# Schematic.net
KiCad netlist of a schematic drawn in EAGLE
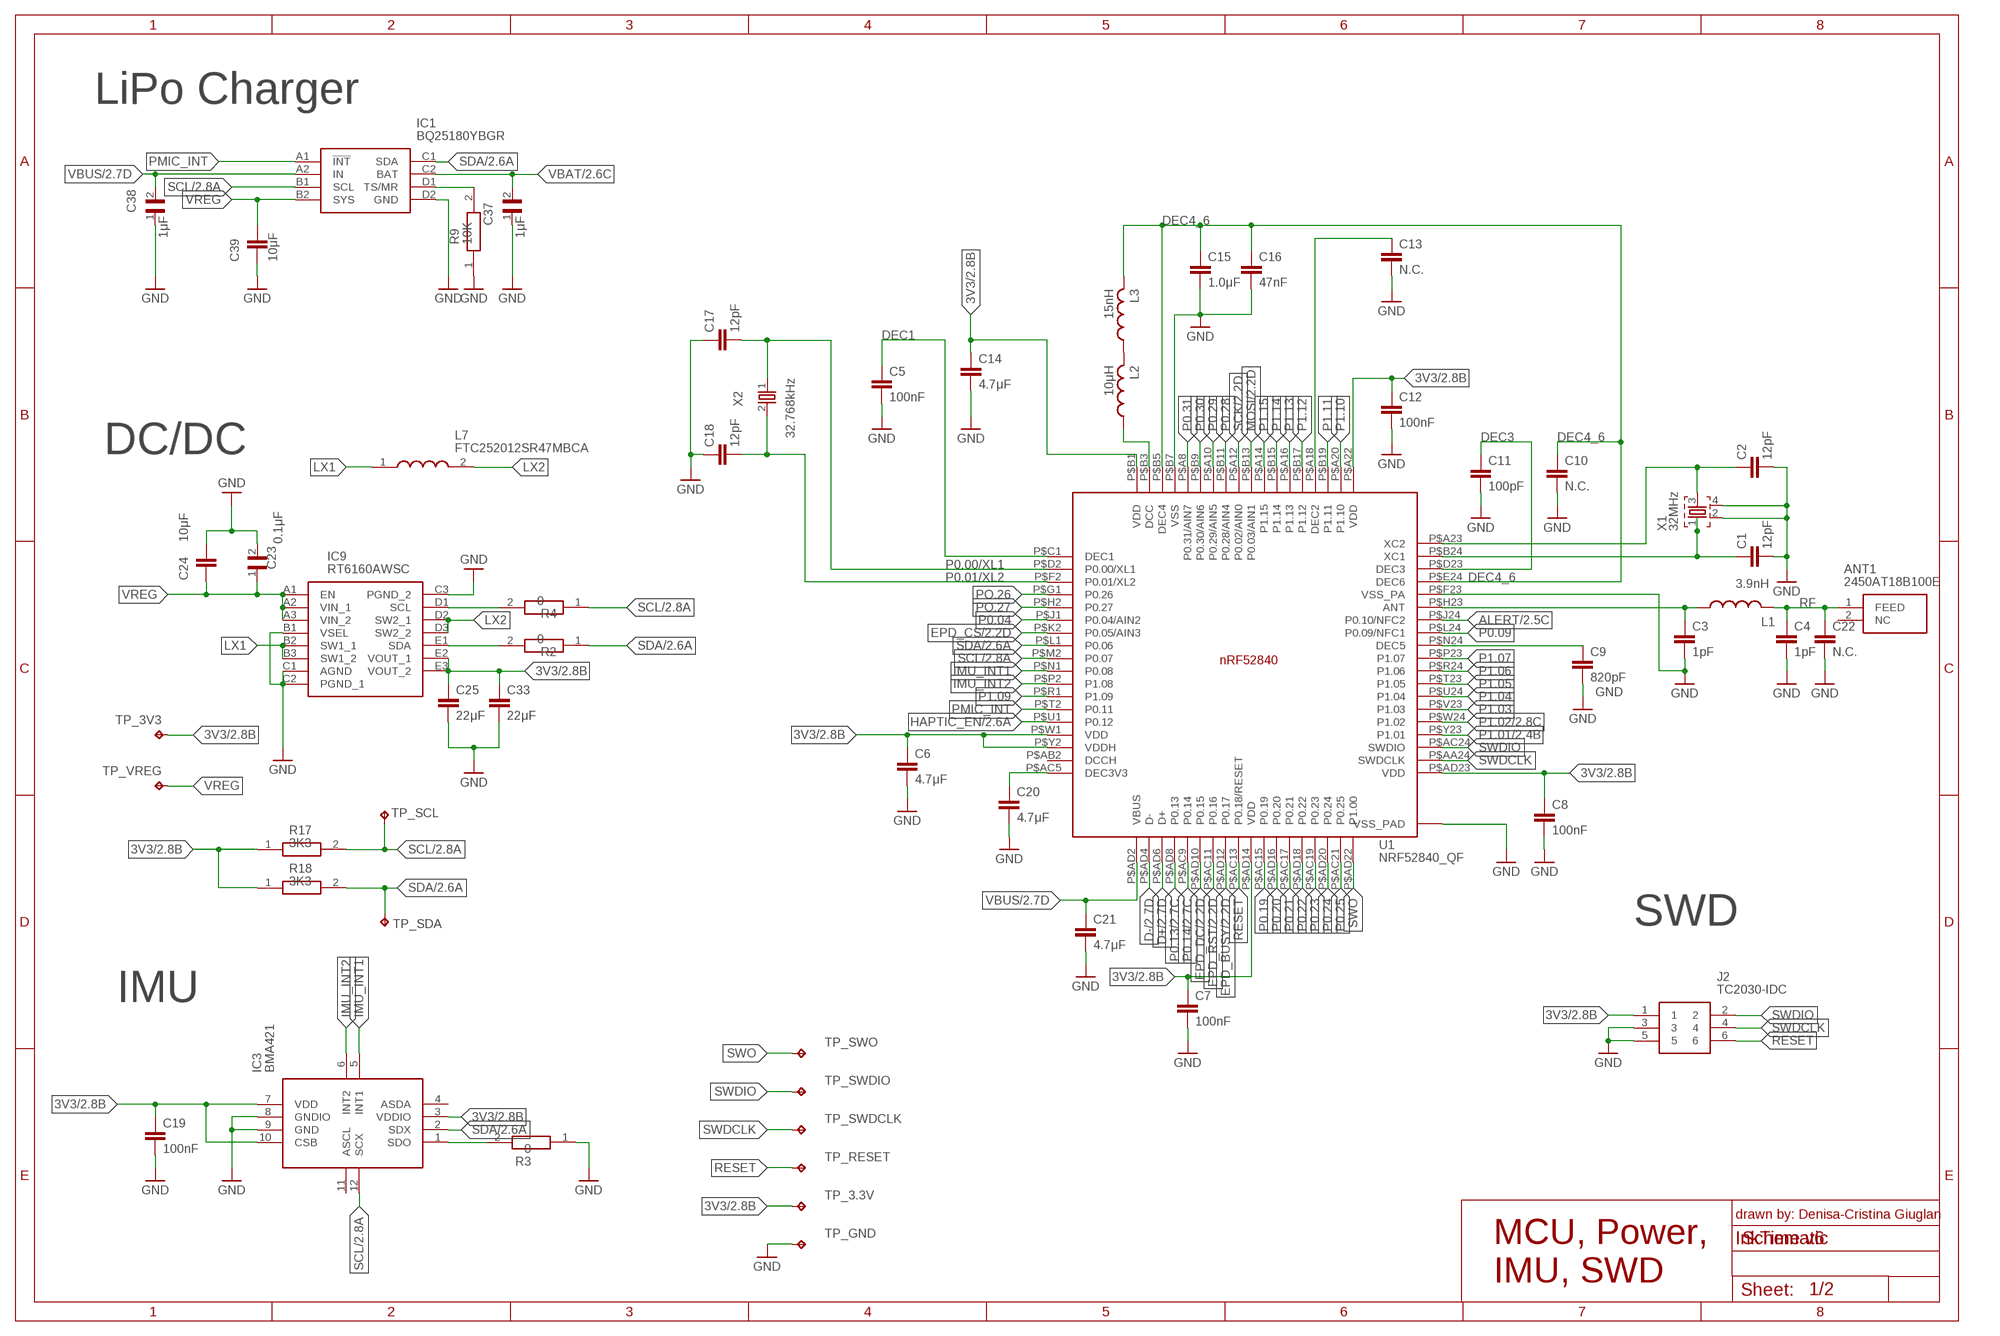
[diagram p0: schematic, sheet 1]
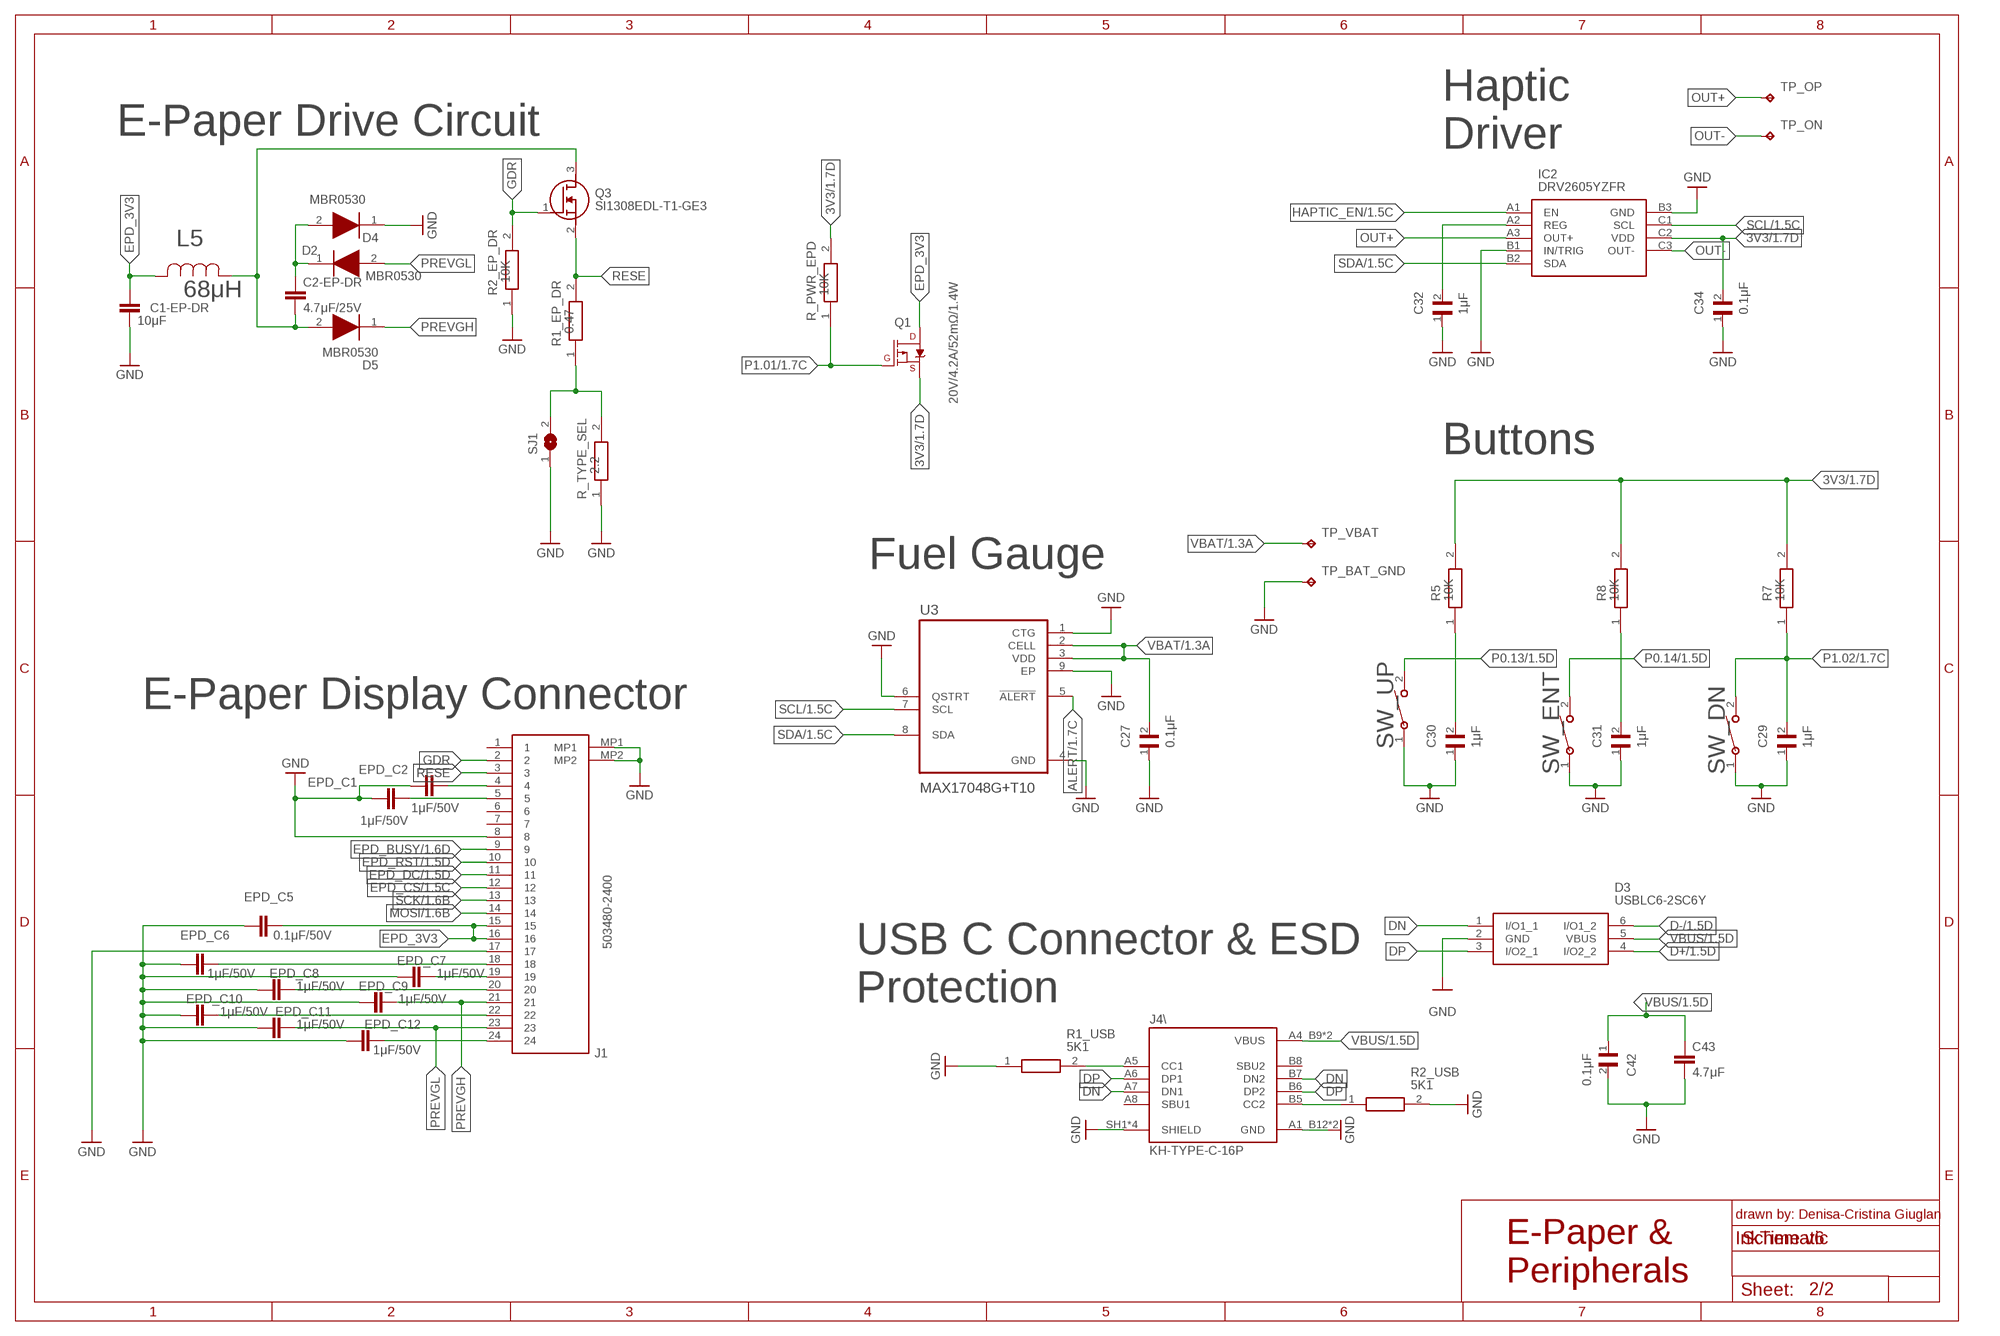
[diagram p1: schematic, sheet 2]

(export (version "E")
  (design (tool "Eeschema 10.0.6"))
  (components
    (comp (ref "ANT1")
      (value "2450AT18B100E")
      (footprint "eagle-import:2450AT18B100E_ANTC3216X140N")
      (fields (field (name "MOUSER_PART_NUMBER") "609-2450AT18B100E"))
      (libsource (lib "eagle-import") (part "2450AT18B100E_2450AT18B100E"))
    )
    (comp (ref "C1")
      (value "12pF")
      (footprint "eagle-import:NORDIC_NRF_3_RESC0201_L")
      (libsource (lib "eagle-import") (part "NORDIC_NRF_3_CAPACITOR_0201_L"))
    )
    (comp (ref "C2")
      (value "12pF")
      (footprint "eagle-import:NORDIC_NRF_3_RESC0201_L")
      (libsource (lib "eagle-import") (part "NORDIC_NRF_3_CAPACITOR_0201_L"))
    )
    (comp (ref "C3")
      (value "1pF")
      (footprint "eagle-import:NORDIC_NRF_3_RESC0402_N")
      (libsource (lib "eagle-import") (part "NORDIC_NRF_3_CAPACITOR_0402_N"))
    )
    (comp (ref "C4")
      (value "1pF")
      (footprint "eagle-import:NORDIC_NRF_3_RESC0201_L")
      (libsource (lib "eagle-import") (part "NORDIC_NRF_3_CAPACITOR_0201_L"))
    )
    (comp (ref "C5")
      (value "100nF")
      (footprint "eagle-import:NORDIC_NRF_3_RESC0201_L")
      (libsource (lib "eagle-import") (part "NORDIC_NRF_3_CAPACITOR_0201_L"))
    )
    (comp (ref "C6")
      (value "4.7μF")
      (footprint "eagle-import:NORDIC_NRF_3_RESC0402_N")
      (libsource (lib "eagle-import") (part "NORDIC_NRF_3_CAPACITOR_0402_N"))
    )
    (comp (ref "C7")
      (value "100nF")
      (footprint "eagle-import:NORDIC_NRF_3_RESC0201_L")
      (libsource (lib "eagle-import") (part "NORDIC_NRF_3_CAPACITOR_0201_L"))
    )
    (comp (ref "C8")
      (value "100nF")
      (footprint "eagle-import:NORDIC_NRF_3_RESC0201_L")
      (libsource (lib "eagle-import") (part "NORDIC_NRF_3_CAPACITOR_0201_L"))
    )
    (comp (ref "C9")
      (value "820pF")
      (footprint "eagle-import:NORDIC_NRF_3_RESC0201_L")
      (libsource (lib "eagle-import") (part "NORDIC_NRF_3_CAPACITOR_0201_L"))
    )
    (comp (ref "C10")
      (value "N.C.")
      (footprint "eagle-import:NORDIC_NRF_3_RESC0402_N")
      (libsource (lib "eagle-import") (part "NORDIC_NRF_3_CAPACITOR_0402_N"))
    )
    (comp (ref "C11")
      (value "100pF")
      (footprint "eagle-import:NORDIC_NRF_3_RESC0402_N")
      (libsource (lib "eagle-import") (part "NORDIC_NRF_3_CAPACITOR_0402_N"))
    )
    (comp (ref "C12")
      (value "100nF")
      (footprint "eagle-import:NORDIC_NRF_3_RESC0201_L")
      (libsource (lib "eagle-import") (part "NORDIC_NRF_3_CAPACITOR_0201_L"))
    )
    (comp (ref "C13")
      (value "N.C.")
      (footprint "eagle-import:NORDIC_NRF_3_RESC0402_N")
      (libsource (lib "eagle-import") (part "NORDIC_NRF_3_CAPACITOR_0402_N"))
    )
    (comp (ref "C14")
      (value "4.7μF")
      (footprint "eagle-import:NORDIC_NRF_3_RESC0402_N")
      (libsource (lib "eagle-import") (part "NORDIC_NRF_3_CAPACITOR_0402_N"))
    )
    (comp (ref "C15")
      (value "1.0μF")
      (footprint "eagle-import:NORDIC_NRF_3_RESC0402_N")
      (libsource (lib "eagle-import") (part "NORDIC_NRF_3_CAPACITOR_0402_N"))
    )
    (comp (ref "C16")
      (value "47nF")
      (footprint "eagle-import:NORDIC_NRF_3_RESC0201_L")
      (libsource (lib "eagle-import") (part "NORDIC_NRF_3_CAPACITOR_0201_L"))
    )
    (comp (ref "C17")
      (value "12pF")
      (footprint "eagle-import:NORDIC_NRF_3_RESC0201_L")
      (libsource (lib "eagle-import") (part "NORDIC_NRF_3_CAPACITOR_0201_L"))
    )
    (comp (ref "C18")
      (value "12pF")
      (footprint "eagle-import:NORDIC_NRF_3_RESC0201_L")
      (libsource (lib "eagle-import") (part "NORDIC_NRF_3_CAPACITOR_0201_L"))
    )
    (comp (ref "C19")
      (value "100nF")
      (footprint "eagle-import:NORDIC_NRF_3_RESC0201_L")
      (libsource (lib "eagle-import") (part "NORDIC_NRF_3_CAPACITOR_0201_L"))
    )
    (comp (ref "C20")
      (value "4.7μF")
      (footprint "eagle-import:NORDIC_NRF_3_RESC0402_N")
      (libsource (lib "eagle-import") (part "NORDIC_NRF_3_CAPACITOR_0402_N"))
    )
    (comp (ref "C21")
      (value "4.7μF")
      (footprint "eagle-import:NORDIC_NRF_3_RESC0402_N")
      (libsource (lib "eagle-import") (part "NORDIC_NRF_3_CAPACITOR_0402_N"))
    )
    (comp (ref "C22")
      (value "N.C.")
      (footprint "eagle-import:NORDIC_NRF_3_RESC0402_N")
      (libsource (lib "eagle-import") (part "NORDIC_NRF_3_CAPACITOR_0402_N"))
    )
    (comp (ref "C23")
      (value "0.1μF")
      (footprint "eagle-import:GRM011R60J152KE01L_2_CAPC0201X13N")
      (fields (field (name "MF") "Murata") (field (name "MP") "GRM011R60J152KE01L"))
      (libsource (lib "eagle-import") (part "GRM011R60J152KE01L_2_GRM011R60J152KE01L"))
    )
    (comp (ref "C24")
      (value "10μF")
      (footprint "eagle-import:NORDIC_NRF_3_RESC0402_N")
      (libsource (lib "eagle-import") (part "NORDIC_NRF_3_CAPACITOR_0402_N"))
    )
    (comp (ref "C25")
      (value "22μF")
      (footprint "eagle-import:NORDIC_NRF_3_RESC0402_N")
      (libsource (lib "eagle-import") (part "NORDIC_NRF_3_CAPACITOR_0402_N"))
    )
    (comp (ref "C33")
      (value "22μF")
      (footprint "eagle-import:NORDIC_NRF_3_RESC0402_N")
      (libsource (lib "eagle-import") (part "NORDIC_NRF_3_CAPACITOR_0402_N"))
    )
    (comp (ref "C37")
      (value "1μF")
      (footprint "eagle-import:GRM011R60J152KE01L_2_CAPC0201X13N")
      (fields (field (name "MF") "Murata") (field (name "MP") "GRM011R60J152KE01L"))
      (libsource (lib "eagle-import") (part "GRM011R60J152KE01L_2_GRM011R60J152KE01L"))
    )
    (comp (ref "C38")
      (value "1μF")
      (footprint "eagle-import:GRM011R60J152KE01L_2_CAPC0201X13N")
      (fields (field (name "MF") "Murata") (field (name "MP") "GRM011R60J152KE01L"))
      (libsource (lib "eagle-import") (part "GRM011R60J152KE01L_2_GRM011R60J152KE01L"))
    )
    (comp (ref "C39")
      (value "10μF")
      (footprint "eagle-import:NORDIC_NRF_3_RESC0402_N")
      (libsource (lib "eagle-import") (part "NORDIC_NRF_3_CAPACITOR_0402_N"))
    )
    (comp (ref "IC1")
      (value "BQ25180YBGR")
      (footprint "eagle-import:BQ25180YBGR_BGA8C40P2X4_100X155X50")
      (fields (field (name "MOUSER_PART_NUMBER") "595-BQ25180YBGR"))
      (libsource (lib "eagle-import") (part "BQ25180YBGR_BQ25180YBGR"))
    )
    (comp (ref "IC3")
      (value "BMA421")
      (footprint "eagle-import:BMA423_BMA423")
      (fields (field (name "ARROW_PART_NUMBER") "BMA423") (field (name "MOUSER_PART_NUMBER") "262-BMA423"))
      (libsource (lib "eagle-import") (part "BMA423_BMA423"))
    )
    (comp (ref "IC9")
      (value "RT6160AWSC")
      (footprint "eagle-import:RT6160AWSC_BGA15C40P3X5_140X230X60")
      (fields (field (name "MOUSER_PART_NUMBER") "835-RT6160AWSC"))
      (libsource (lib "eagle-import") (part "RT6160AWSC_RT6160AWSC"))
    )
    (comp (ref "J2")
      (value "TC2030-IDC")
      (footprint "eagle-import:TC2030-IDC_TC2030IDC")
      (libsource (lib "eagle-import") (part "TC2030-IDC_TC2030-IDC"))
    )
    (comp (ref "L1")
      (value "3.9nH")
      (footprint "eagle-import:NORDIC_NRF_2_RESC0402_L")
      (libsource (lib "eagle-import") (part "NORDIC_NRF_2_INDUCTOR_0402_L"))
    )
    (comp (ref "L2")
      (value "10μH")
      (footprint "eagle-import:NORDIC_NRF_2_RESC0402_L")
      (libsource (lib "eagle-import") (part "NORDIC_NRF_2_INDUCTOR_0402_L"))
    )
    (comp (ref "L3")
      (value "15nH")
      (footprint "eagle-import:NORDIC_NRF_2_RESC0402_L")
      (libsource (lib "eagle-import") (part "NORDIC_NRF_2_INDUCTOR_0402_L"))
    )
    (comp (ref "L7")
      (value "FTC252012SR47MBCA")
      (footprint "eagle-import:MLP2016SR47MT0S1_INDC2016X100N")
      (libsource (lib "eagle-import") (part "MLP2016SR47MT0S1_FTC252012SR47MBCA"))
    )
    (comp (ref "R2")
      (value "0")
      (footprint "eagle-import:CPF0201D7K68C1_0201")
      (libsource (lib "eagle-import") (part "CPF0201D7K68C1_CPF0201D7K68C1"))
    )
    (comp (ref "R3")
      (value "0")
      (footprint "eagle-import:CPF0201D7K68C1_0201")
      (libsource (lib "eagle-import") (part "CPF0201D7K68C1_CPF0201D7K68C1"))
    )
    (comp (ref "R4")
      (value "0")
      (footprint "eagle-import:CPF0201D7K68C1_0201")
      (libsource (lib "eagle-import") (part "CPF0201D7K68C1_CPF0201D7K68C1"))
    )
    (comp (ref "R9")
      (value "10K")
      (footprint "eagle-import:CPF0201D7K68C1_0201")
      (libsource (lib "eagle-import") (part "CPF0201D7K68C1_CPF0201D7K68C1"))
    )
    (comp (ref "R17")
      (value "3K3")
      (footprint "eagle-import:CPF0201D7K68C1_0201")
      (libsource (lib "eagle-import") (part "CPF0201D7K68C1_CPF0201D7K68C1"))
    )
    (comp (ref "R18")
      (value "3K3")
      (footprint "eagle-import:CPF0201D7K68C1_0201")
      (libsource (lib "eagle-import") (part "CPF0201D7K68C1_CPF0201D7K68C1"))
    )
    (comp (ref "TP_3.3V")
      (value "HECTOR_WATCH_1_TPTP20R")
      (footprint "eagle-import:HECTOR_WATCH_1_TP20R")
      (libsource (lib "eagle-import") (part "HECTOR_WATCH_1_TPTP20R"))
    )
    (comp (ref "TP_3V3")
      (value "HECTOR_WATCH_1_TPTP20R")
      (footprint "eagle-import:HECTOR_WATCH_1_TP20R")
      (libsource (lib "eagle-import") (part "HECTOR_WATCH_1_TPTP20R"))
    )
    (comp (ref "TP_GND")
      (value "HECTOR_WATCH_1_TPTP20R")
      (footprint "eagle-import:HECTOR_WATCH_1_TP20R")
      (libsource (lib "eagle-import") (part "HECTOR_WATCH_1_TPTP20R"))
    )
    (comp (ref "TP_RESET")
      (value "HECTOR_WATCH_1_TPTP20R")
      (footprint "eagle-import:HECTOR_WATCH_1_TP20R")
      (libsource (lib "eagle-import") (part "HECTOR_WATCH_1_TPTP20R"))
    )
    (comp (ref "TP_SCL")
      (value "HECTOR_WATCH_1_TPTP20R")
      (footprint "eagle-import:HECTOR_WATCH_1_TP20R")
      (libsource (lib "eagle-import") (part "HECTOR_WATCH_1_TPTP20R"))
    )
    (comp (ref "TP_SDA")
      (value "HECTOR_WATCH_1_TPTP20R")
      (footprint "eagle-import:HECTOR_WATCH_1_TP20R")
      (libsource (lib "eagle-import") (part "HECTOR_WATCH_1_TPTP20R"))
    )
    (comp (ref "TP_SWDCLK")
      (value "HECTOR_WATCH_1_TPTP20R")
      (footprint "eagle-import:HECTOR_WATCH_1_TP20R")
      (libsource (lib "eagle-import") (part "HECTOR_WATCH_1_TPTP20R"))
    )
    (comp (ref "TP_SWDIO")
      (value "HECTOR_WATCH_1_TPTP20R")
      (footprint "eagle-import:HECTOR_WATCH_1_TP20R")
      (libsource (lib "eagle-import") (part "HECTOR_WATCH_1_TPTP20R"))
    )
    (comp (ref "TP_SWO")
      (value "HECTOR_WATCH_1_TPTP20R")
      (footprint "eagle-import:HECTOR_WATCH_1_TP20R")
      (libsource (lib "eagle-import") (part "HECTOR_WATCH_1_TPTP20R"))
    )
    (comp (ref "TP_VREG")
      (value "HECTOR_WATCH_1_TPTP20R")
      (footprint "eagle-import:HECTOR_WATCH_1_TP20R")
      (libsource (lib "eagle-import") (part "HECTOR_WATCH_1_TPTP20R"))
    )
    (comp (ref "U1")
      (value "NRF52840_QF")
      (footprint "eagle-import:NORDIC_NRF_4_AQFN50P700X700X85_HS-74N")
      (libsource (lib "eagle-import") (part "NORDIC_NRF_4_NRF52840_QF"))
    )
    (comp (ref "X1")
      (value "32MHz")
      (footprint "eagle-import:NORDIC_NRF_BT-XTAL_2016_N")
      (libsource (lib "eagle-import") (part "NORDIC_NRF_XTAL_32MHZ"))
    )
    (comp (ref "X2")
      (value "32.768kHz")
      (footprint "eagle-import:NORDIC_NRF_1_XTAL_3215_N")
      (libsource (lib "eagle-import") (part "NORDIC_NRF_1_XTAL_32KHZ"))
    )
    (comp (ref "C1-EP-DR")
      (value "10μF")
      (footprint "eagle-import:NORDIC_NRF_3_RESC0402_N")
      (libsource (lib "eagle-import") (part "NORDIC_NRF_3_CAPACITOR_0402_N"))
    )
    (comp (ref "C2-EP-DR")
      (value "4.7μF/25V")
      (footprint "eagle-import:NORDIC_NRF_3_RESC0402_N")
      (libsource (lib "eagle-import") (part "NORDIC_NRF_3_CAPACITOR_0402_N"))
    )
    (comp (ref "C27")
      (value "0.1μF")
      (footprint "eagle-import:GRM011R60J152KE01L_2_CAPC0201X13N")
      (fields (field (name "MF") "Murata") (field (name "MP") "GRM011R60J152KE01L"))
      (libsource (lib "eagle-import") (part "GRM011R60J152KE01L_2_GRM011R60J152KE01L"))
    )
    (comp (ref "C29")
      (value "1μF")
      (footprint "eagle-import:GRM011R60J152KE01L_2_CAPC0201X13N")
      (fields (field (name "MF") "Murata") (field (name "MP") "GRM011R60J152KE01L"))
      (libsource (lib "eagle-import") (part "GRM011R60J152KE01L_2_GRM011R60J152KE01L"))
    )
    (comp (ref "C30")
      (value "1μF")
      (footprint "eagle-import:GRM011R60J152KE01L_2_CAPC0201X13N")
      (fields (field (name "MF") "Murata") (field (name "MP") "GRM011R60J152KE01L"))
      (libsource (lib "eagle-import") (part "GRM011R60J152KE01L_2_GRM011R60J152KE01L"))
    )
    (comp (ref "C31")
      (value "1μF")
      (footprint "eagle-import:GRM011R60J152KE01L_2_CAPC0201X13N")
      (fields (field (name "MF") "Murata") (field (name "MP") "GRM011R60J152KE01L"))
      (libsource (lib "eagle-import") (part "GRM011R60J152KE01L_2_GRM011R60J152KE01L"))
    )
    (comp (ref "C32")
      (value "1μF")
      (footprint "eagle-import:GRM011R60J152KE01L_2_CAPC0201X13N")
      (fields (field (name "MF") "Murata") (field (name "MP") "GRM011R60J152KE01L"))
      (libsource (lib "eagle-import") (part "GRM011R60J152KE01L_2_GRM011R60J152KE01L"))
    )
    (comp (ref "C34")
      (value "0.1μF")
      (footprint "eagle-import:GRM011R60J152KE01L_2_CAPC0201X13N")
      (fields (field (name "MF") "Murata") (field (name "MP") "GRM011R60J152KE01L"))
      (libsource (lib "eagle-import") (part "GRM011R60J152KE01L_2_GRM011R60J152KE01L"))
    )
    (comp (ref "C42")
      (value "0.1μF")
      (footprint "eagle-import:GRM011R60J152KE01L_2_CAPC0201X13N")
      (fields (field (name "MF") "Murata") (field (name "MP") "GRM011R60J152KE01L"))
      (libsource (lib "eagle-import") (part "GRM011R60J152KE01L_2_GRM011R60J152KE01L"))
    )
    (comp (ref "C43")
      (value "4.7μF")
      (footprint "eagle-import:NORDIC_NRF_3_RESC0402_N")
      (libsource (lib "eagle-import") (part "NORDIC_NRF_3_CAPACITOR_0402_N"))
    )
    (comp (ref "D2")
      (value "MBR0530")
      (footprint "eagle-import:ESP32_C6_LIBRARY_5_SOD3716X135N")
      (fields (field (name "MF") "ON Semiconductor"))
      (libsource (lib "eagle-import") (part "ESP32_C6_LIBRARY_5_MBR0530"))
    )
    (comp (ref "D3")
      (value "USBLC6-2SC6Y")
      (footprint "eagle-import:ESP32_C6_LIBRARY_3_SOT95P280X145-6N")
      (fields (field (name "MF") "STMicroelectronics"))
      (libsource (lib "eagle-import") (part "ESP32_C6_LIBRARY_3_USBLC6-2SC6Y"))
    )
    (comp (ref "D4")
      (value "MBR0530")
      (footprint "eagle-import:ESP32_C6_LIBRARY_5_SOD3716X135N")
      (fields (field (name "MF") "ON Semiconductor"))
      (libsource (lib "eagle-import") (part "ESP32_C6_LIBRARY_5_MBR0530"))
    )
    (comp (ref "D5")
      (value "MBR0530")
      (footprint "eagle-import:ESP32_C6_LIBRARY_5_SOD3716X135N")
      (fields (field (name "MF") "ON Semiconductor"))
      (libsource (lib "eagle-import") (part "ESP32_C6_LIBRARY_5_MBR0530"))
    )
    (comp (ref "EPD_C1")
      (value "1μF/50V")
      (footprint "eagle-import:NORDIC_NRF_3_RESC0402_N")
      (libsource (lib "eagle-import") (part "NORDIC_NRF_3_CAPACITOR_0402_N"))
    )
    (comp (ref "EPD_C2")
      (value "1μF/50V")
      (footprint "eagle-import:NORDIC_NRF_3_RESC0402_N")
      (libsource (lib "eagle-import") (part "NORDIC_NRF_3_CAPACITOR_0402_N"))
    )
    (comp (ref "EPD_C5")
      (value "0.1μF/50V")
      (footprint "eagle-import:NORDIC_NRF_3_RESC0402_N")
      (libsource (lib "eagle-import") (part "NORDIC_NRF_3_CAPACITOR_0402_N"))
    )
    (comp (ref "EPD_C6")
      (value "1μF/50V")
      (footprint "eagle-import:NORDIC_NRF_3_RESC0402_N")
      (libsource (lib "eagle-import") (part "NORDIC_NRF_3_CAPACITOR_0402_N"))
    )
    (comp (ref "EPD_C7")
      (value "1μF/50V")
      (footprint "eagle-import:NORDIC_NRF_3_RESC0402_N")
      (libsource (lib "eagle-import") (part "NORDIC_NRF_3_CAPACITOR_0402_N"))
    )
    (comp (ref "EPD_C8")
      (value "1μF/50V")
      (footprint "eagle-import:NORDIC_NRF_3_RESC0402_N")
      (libsource (lib "eagle-import") (part "NORDIC_NRF_3_CAPACITOR_0402_N"))
    )
    (comp (ref "EPD_C9")
      (value "1μF/50V")
      (footprint "eagle-import:NORDIC_NRF_3_RESC0402_N")
      (libsource (lib "eagle-import") (part "NORDIC_NRF_3_CAPACITOR_0402_N"))
    )
    (comp (ref "EPD_C10")
      (value "1μF/50V")
      (footprint "eagle-import:NORDIC_NRF_3_RESC0402_N")
      (libsource (lib "eagle-import") (part "NORDIC_NRF_3_CAPACITOR_0402_N"))
    )
    (comp (ref "EPD_C11")
      (value "1μF/50V")
      (footprint "eagle-import:NORDIC_NRF_3_RESC0402_N")
      (libsource (lib "eagle-import") (part "NORDIC_NRF_3_CAPACITOR_0402_N"))
    )
    (comp (ref "EPD_C12")
      (value "1μF/50V")
      (footprint "eagle-import:NORDIC_NRF_3_RESC0402_N")
      (libsource (lib "eagle-import") (part "NORDIC_NRF_3_CAPACITOR_0402_N"))
    )
    (comp (ref "IC2")
      (value "DRV2605YZFR")
      (footprint "eagle-import:DRV2605YZFR_BGA9C50P3X3_144X144X62")
      (libsource (lib "eagle-import") (part "DRV2605YZFR_DRV2605YZFR"))
    )
    (comp (ref "J1")
      (value "503480-2400")
      (footprint "eagle-import:503480-2400_5034802400")
      (fields (field (name "MOUSER_PART_NUMBER") "538-503480-2400"))
      (libsource (lib "eagle-import") (part "503480-2400_503480-2400"))
    )
    (comp (ref "J4\\")
      (value "KH-TYPE-C-16P")
      (footprint "eagle-import:KH-TYPE-C-16P_KINGHELM_KH-TYPE-C-16P")
      (fields (field (name "MF") "kinghelm"))
      (libsource (lib "eagle-import") (part "KH-TYPE-C-16P_KH-TYPE-C-16P"))
    )
    (comp (ref "L5")
      (value "68μH")
      (footprint "eagle-import:ESP32_C6_LIBRARY_2_IND_4828-WE-TPC_WRE")
      (fields
        (field (name "MANUFACTURER_PART_NUMBER") "744043680")
        (field (name "COPYRIGHT") "Copyright (C) 2024 Ultra Librarian. All rights reserved.")
      )
      (libsource (lib "eagle-import") (part "ESP32_C6_LIBRARY_2_744043680IND_4828-WE-TPC_WRE"))
    )
    (comp (ref "Q1")
      (value "20V/4.2A/52mΩ/1.4W")
      (footprint "eagle-import:ESP32_C6_LIBRARY_4_ESP32_C6_LIBRARY_4_ESP32_C6_LIBRARY_4_ESP32_C6_LIBRARY_4_ESP32_WROVER_SPARKFUN-DISCRETESEMI_SOT23-3")
      (libsource (lib "eagle-import") (part "ESP32_C6_LIBRARY_4_ESP32_WROVER_SPARKFUN-DISCRETESEMI_MOSFET_PCH-DMG2305UX-7"))
    )
    (comp (ref "Q3")
      (value "SI1308EDL-T1-GE3")
      (footprint "eagle-import:ESP32_C6_LIBRARY_6_SOT65P210X110-3N")
      (fields (field (name "MF") "Vishay Siliconix"))
      (libsource (lib "eagle-import") (part "ESP32_C6_LIBRARY_6_SI1308EDL-T1-GE3"))
    )
    (comp (ref "R1_EP_DR")
      (value "0.47")
      (footprint "eagle-import:CPF0201D7K68C1_0201")
      (libsource (lib "eagle-import") (part "CPF0201D7K68C1_CPF0201D7K68C1"))
    )
    (comp (ref "R1_USB")
      (value "5K1")
      (footprint "eagle-import:CPF0201D7K68C1_0201")
      (libsource (lib "eagle-import") (part "CPF0201D7K68C1_CPF0201D7K68C1"))
    )
    (comp (ref "R2_EP_DR")
      (value "10K")
      (footprint "eagle-import:CPF0201D7K68C1_0201")
      (libsource (lib "eagle-import") (part "CPF0201D7K68C1_CPF0201D7K68C1"))
    )
    (comp (ref "R2_USB")
      (value "5K1")
      (footprint "eagle-import:CPF0201D7K68C1_0201")
      (libsource (lib "eagle-import") (part "CPF0201D7K68C1_CPF0201D7K68C1"))
    )
    (comp (ref "R5")
      (value "10K")
      (footprint "eagle-import:CPF0201D7K68C1_0201")
      (libsource (lib "eagle-import") (part "CPF0201D7K68C1_CPF0201D7K68C1"))
    )
    (comp (ref "R7")
      (value "10K")
      (footprint "eagle-import:CPF0201D7K68C1_0201")
      (libsource (lib "eagle-import") (part "CPF0201D7K68C1_CPF0201D7K68C1"))
    )
    (comp (ref "R8")
      (value "10K")
      (footprint "eagle-import:CPF0201D7K68C1_0201")
      (libsource (lib "eagle-import") (part "CPF0201D7K68C1_CPF0201D7K68C1"))
    )
    (comp (ref "R_PWR_EPD")
      (value "10K")
      (footprint "eagle-import:CPF0201D7K68C1_0201")
      (libsource (lib "eagle-import") (part "CPF0201D7K68C1_CPF0201D7K68C1"))
    )
    (comp (ref "R_TYPE_SEL")
      (value "2.2")
      (footprint "eagle-import:CPF0201D7K68C1_0201")
      (libsource (lib "eagle-import") (part "CPF0201D7K68C1_CPF0201D7K68C1"))
    )
    (comp (ref "SJ1")
      (value "ESP32_C6_LIBRARY_7_JUMPER_SJ")
      (footprint "eagle-import:ESP32_C6_LIBRARY_7_JUMPER_SJ")
      (libsource (lib "eagle-import") (part "ESP32_C6_LIBRARY_7_JUMPER_SJ"))
    )
    (comp (ref "SW_DN")
      (value "2025-10-22_07-23-44_LIBRARY_EVP-AKE31ASW_EVP-AKE31A_PAN")
      (footprint "eagle-import:2025-10-22_07-23-44_LIBRARY_SW_EVP-AKE31A_PAN")
      (fields
        (field (name "MANUFACTURER_PART_NUMBER") "EVP-AKE31A")
        (field (name "COPYRIGHT") "Copyright (C) 2025 Ultra Librarian. All rights reserved.")
      )
      (libsource (lib "eagle-import") (part "2025-10-22_07-23-44_LIBRARY_EVP-AKE31ASW_EVP-AKE31A_PAN"))
    )
    (comp (ref "SW_ENT")
      (value "2025-10-22_07-23-44_LIBRARY_EVP-AKE31ASW_EVP-AKE31A_PAN")
      (footprint "eagle-import:2025-10-22_07-23-44_LIBRARY_SW_EVP-AKE31A_PAN")
      (fields
        (field (name "MANUFACTURER_PART_NUMBER") "EVP-AKE31A")
        (field (name "COPYRIGHT") "Copyright (C) 2025 Ultra Librarian. All rights reserved.")
      )
      (libsource (lib "eagle-import") (part "2025-10-22_07-23-44_LIBRARY_EVP-AKE31ASW_EVP-AKE31A_PAN"))
    )
    (comp (ref "SW_UP")
      (value "2025-10-22_07-23-44_LIBRARY_EVP-AKE31ASW_EVP-AKE31A_PAN")
      (footprint "eagle-import:2025-10-22_07-23-44_LIBRARY_SW_EVP-AKE31A_PAN")
      (fields
        (field (name "MANUFACTURER_PART_NUMBER") "EVP-AKE31A")
        (field (name "COPYRIGHT") "Copyright (C) 2025 Ultra Librarian. All rights reserved.")
      )
      (libsource (lib "eagle-import") (part "2025-10-22_07-23-44_LIBRARY_EVP-AKE31ASW_EVP-AKE31A_PAN"))
    )
    (comp (ref "TP_BAT_GND")
      (value "HECTOR_WATCH_1_TPTP20R")
      (footprint "eagle-import:HECTOR_WATCH_1_TP20R")
      (libsource (lib "eagle-import") (part "HECTOR_WATCH_1_TPTP20R"))
    )
    (comp (ref "TP_ON")
      (value "HECTOR_WATCH_1_TPTP20R")
      (footprint "eagle-import:HECTOR_WATCH_1_TP20R")
      (libsource (lib "eagle-import") (part "HECTOR_WATCH_1_TPTP20R"))
    )
    (comp (ref "TP_OP")
      (value "HECTOR_WATCH_1_TPTP20R")
      (footprint "eagle-import:HECTOR_WATCH_1_TP20R")
      (libsource (lib "eagle-import") (part "HECTOR_WATCH_1_TPTP20R"))
    )
    (comp (ref "TP_VBAT")
      (value "HECTOR_WATCH_1_TPTP20R")
      (footprint "eagle-import:HECTOR_WATCH_1_TP20R")
      (libsource (lib "eagle-import") (part "HECTOR_WATCH_1_TPTP20R"))
    )
    (comp (ref "U3")
      (value "MAX17048G+T10")
      (footprint "eagle-import:ESP32_C6_LIBRARY_SON50P200X200X80-9N")
      (fields (field (name "MF") "Analog Devices"))
      (libsource (lib "eagle-import") (part "ESP32_C6_LIBRARY_MAX17048G+T10"))
    )
  )
  (nets
    (net (code "1") (name "3V3") (class "Default")
      (node (ref "C12") (pin "1") (pinfunction "1_1") (pintype "passive"))
      (node (ref "C14") (pin "1") (pinfunction "1_1") (pintype "passive"))
      (node (ref "C19") (pin "1") (pinfunction "1_1") (pintype "passive"))
      (node (ref "C25") (pin "1") (pinfunction "1_1") (pintype "passive"))
      (node (ref "C33") (pin "1") (pinfunction "1_1") (pintype "passive"))
      (node (ref "C34") (pin "2") (pinfunction "2_2") (pintype "passive"))
      (node (ref "C6") (pin "1") (pinfunction "1_1") (pintype "passive"))
      (node (ref "C7") (pin "1") (pinfunction "1_1") (pintype "passive"))
      (node (ref "C8") (pin "1") (pinfunction "1_1") (pintype "passive"))
      (node (ref "IC2") (pin "C2") (pinfunction "VDD_C2") (pintype "bidirectional"))
      (node (ref "IC3") (pin "10") (pinfunction "CSB_10") (pintype "bidirectional"))
      (node (ref "IC3") (pin "3") (pinfunction "VDDIO_3") (pintype "bidirectional"))
      (node (ref "IC3") (pin "7") (pinfunction "VDD_7") (pintype "bidirectional"))
      (node (ref "IC9") (pin "E2") (pinfunction "VOUT_1_E2") (pintype "bidirectional"))
      (node (ref "IC9") (pin "E3") (pinfunction "VOUT_2_E3") (pintype "bidirectional"))
      (node (ref "J2") (pin "1") (pinfunction "1_1") (pintype "bidirectional"))
      (node (ref "Q1") (pin "2") (pinfunction "S_2") (pintype "bidirectional"))
      (node (ref "R17") (pin "1") (pinfunction "1_1") (pintype "bidirectional"))
      (node (ref "R18") (pin "1") (pinfunction "1_1") (pintype "bidirectional"))
      (node (ref "R5") (pin "2") (pinfunction "2_2") (pintype "bidirectional"))
      (node (ref "R7") (pin "2") (pinfunction "2_2") (pintype "bidirectional"))
      (node (ref "R8") (pin "2") (pinfunction "2_2") (pintype "bidirectional"))
      (node (ref "R_PWR_EPD") (pin "2") (pinfunction "2_2") (pintype "bidirectional"))
      (node (ref "TP_3.3V") (pin "TP") (pinfunction "TP_TP") (pintype "input"))
      (node (ref "TP_3V3") (pin "TP") (pinfunction "TP_TP") (pintype "input"))
      (node (ref "U1") (pin "P$A22") (pinfunction "VDD_P$A22") (pintype "power_in"))
      (node (ref "U1") (pin "P$AD14") (pinfunction "VDD_P$AD14") (pintype "power_in"))
      (node (ref "U1") (pin "P$AD23") (pinfunction "VDD_P$AD23") (pintype "power_in"))
      (node (ref "U1") (pin "P$B1") (pinfunction "VDD_P$B1") (pintype "power_in"))
      (node (ref "U1") (pin "P$W1") (pinfunction "VDD_P$W1") (pintype "power_in"))
      (node (ref "U1") (pin "P$Y2") (pinfunction "VDDH_P$Y2") (pintype "power_in"))
    )
    (net (code "2") (name "ALERT") (class "Default")
      (node (ref "U1") (pin "P$J24") (pinfunction "P0.10/NFC2_P$J24") (pintype "bidirectional"))
      (node (ref "U3") (pin "5") (pinfunction "~{ALERT}_5") (pintype "output"))
    )
    (net (code "3") (name "D+") (class "Default")
      (node (ref "D3") (pin "4") (pinfunction "I/O2_2_4") (pintype "bidirectional"))
      (node (ref "U1") (pin "P$AD6") (pinfunction "D+_P$AD6") (pintype "bidirectional"))
    )
    (net (code "4") (name "D-") (class "Default")
      (node (ref "D3") (pin "6") (pinfunction "I/O1_2_6") (pintype "bidirectional"))
      (node (ref "U1") (pin "P$AD4") (pinfunction "D-_P$AD4") (pintype "bidirectional"))
    )
    (net (code "5") (name "DEC1") (class "Default")
      (node (ref "C5") (pin "1") (pinfunction "1_1") (pintype "passive"))
      (node (ref "U1") (pin "P$C1") (pinfunction "DEC1_P$C1") (pintype "power_in"))
    )
    (net (code "6") (name "DEC3") (class "Default")
      (node (ref "C11") (pin "1") (pinfunction "1_1") (pintype "passive"))
      (node (ref "U1") (pin "P$D23") (pinfunction "DEC3_P$D23") (pintype "bidirectional"))
    )
    (net (code "7") (name "DEC4_6") (class "Default")
      (node (ref "C10") (pin "1") (pinfunction "1_1") (pintype "passive"))
      (node (ref "C15") (pin "1") (pinfunction "1_1") (pintype "passive"))
      (node (ref "C16") (pin "1") (pinfunction "1_1") (pintype "passive"))
      (node (ref "L3") (pin "2") (pinfunction "2_2") (pintype "passive"))
      (node (ref "U1") (pin "P$B5") (pinfunction "DEC4_P$B5") (pintype "power_in"))
      (node (ref "U1") (pin "P$E24") (pinfunction "DEC6_P$E24") (pintype "bidirectional"))
    )
    (net (code "8") (name "DN") (class "Default")
      (node (ref "D3") (pin "1") (pinfunction "I/O1_1_1") (pintype "bidirectional"))
      (node (ref "J4\\") (pin "A7") (pinfunction "DN1_A7") (pintype "bidirectional"))
      (node (ref "J4\\") (pin "B7") (pinfunction "DN2_B7") (pintype "bidirectional"))
    )
    (net (code "9") (name "DP") (class "Default")
      (node (ref "D3") (pin "3") (pinfunction "I/O2_1_3") (pintype "bidirectional"))
      (node (ref "J4\\") (pin "A6") (pinfunction "DP1_A6") (pintype "bidirectional"))
      (node (ref "J4\\") (pin "B6") (pinfunction "DP2_B6") (pintype "bidirectional"))
    )
    (net (code "10") (name "EPD_3V3") (class "Default")
      (node (ref "C1-EP-DR") (pin "1") (pinfunction "1_1") (pintype "passive"))
      (node (ref "EPD_C5") (pin "2") (pinfunction "2_2") (pintype "passive"))
      (node (ref "J1") (pin "15") (pinfunction "15_15") (pintype "bidirectional"))
      (node (ref "J1") (pin "16") (pinfunction "16_16") (pintype "bidirectional"))
      (node (ref "L5") (pin "2") (pinfunction "2_2") (pintype "passive"))
      (node (ref "Q1") (pin "3") (pinfunction "D_3") (pintype "bidirectional"))
    )
    (net (code "11") (name "EPD_BUSY") (class "Default")
      (node (ref "J1") (pin "9") (pinfunction "9_9") (pintype "bidirectional"))
      (node (ref "U1") (pin "P$AD12") (pinfunction "P0.17_P$AD12") (pintype "bidirectional"))
    )
    (net (code "12") (name "EPD_CS") (class "Default")
      (node (ref "J1") (pin "12") (pinfunction "12_12") (pintype "bidirectional"))
      (node (ref "U1") (pin "P$K2") (pinfunction "P0.05/AIN3_P$K2") (pintype "bidirectional"))
    )
    (net (code "13") (name "EPD_DC") (class "Default")
      (node (ref "J1") (pin "11") (pinfunction "11_11") (pintype "bidirectional"))
      (node (ref "U1") (pin "P$AD10") (pinfunction "P0.15_P$AD10") (pintype "bidirectional"))
    )
    (net (code "14") (name "EPD_RST") (class "Default")
      (node (ref "J1") (pin "10") (pinfunction "10_10") (pintype "bidirectional"))
      (node (ref "U1") (pin "P$AC11") (pinfunction "P0.16_P$AC11") (pintype "bidirectional"))
    )
    (net (code "15") (name "GDR") (class "Default")
      (node (ref "J1") (pin "2") (pinfunction "2_2") (pintype "bidirectional"))
      (node (ref "Q3") (pin "1") (pinfunction "G_1") (pintype "bidirectional"))
      (node (ref "R2_EP_DR") (pin "2") (pinfunction "2_2") (pintype "bidirectional"))
    )
    (net (code "16") (name "GND") (class "Default")
      (node (ref "C1") (pin "2") (pinfunction "2_2") (pintype "passive"))
      (node (ref "C1-EP-DR") (pin "2") (pinfunction "2_2") (pintype "passive"))
      (node (ref "C10") (pin "2") (pinfunction "2_2") (pintype "passive"))
      (node (ref "C11") (pin "2") (pinfunction "2_2") (pintype "passive"))
      (node (ref "C12") (pin "2") (pinfunction "2_2") (pintype "passive"))
      (node (ref "C13") (pin "2") (pinfunction "2_2") (pintype "passive"))
      (node (ref "C14") (pin "2") (pinfunction "2_2") (pintype "passive"))
      (node (ref "C15") (pin "2") (pinfunction "2_2") (pintype "passive"))
      (node (ref "C16") (pin "2") (pinfunction "2_2") (pintype "passive"))
      (node (ref "C17") (pin "1") (pinfunction "1_1") (pintype "passive"))
      (node (ref "C18") (pin "1") (pinfunction "1_1") (pintype "passive"))
      (node (ref "C19") (pin "2") (pinfunction "2_2") (pintype "passive"))
      (node (ref "C2") (pin "2") (pinfunction "2_2") (pintype "passive"))
      (node (ref "C20") (pin "2") (pinfunction "2_2") (pintype "passive"))
      (node (ref "C21") (pin "2") (pinfunction "2_2") (pintype "passive"))
      (node (ref "C22") (pin "2") (pinfunction "2_2") (pintype "passive"))
      (node (ref "C23") (pin "2") (pinfunction "2_2") (pintype "passive"))
      (node (ref "C24") (pin "1") (pinfunction "1_1") (pintype "passive"))
      (node (ref "C25") (pin "2") (pinfunction "2_2") (pintype "passive"))
      (node (ref "C27") (pin "1") (pinfunction "1_1") (pintype "passive"))
      (node (ref "C29") (pin "1") (pinfunction "1_1") (pintype "passive"))
      (node (ref "C3") (pin "2") (pinfunction "2_2") (pintype "passive"))
      (node (ref "C30") (pin "1") (pinfunction "1_1") (pintype "passive"))
      (node (ref "C31") (pin "1") (pinfunction "1_1") (pintype "passive"))
      (node (ref "C32") (pin "1") (pinfunction "1_1") (pintype "passive"))
      (node (ref "C33") (pin "2") (pinfunction "2_2") (pintype "passive"))
      (node (ref "C34") (pin "1") (pinfunction "1_1") (pintype "passive"))
      (node (ref "C37") (pin "1") (pinfunction "1_1") (pintype "passive"))
      (node (ref "C38") (pin "1") (pinfunction "1_1") (pintype "passive"))
      (node (ref "C39") (pin "2") (pinfunction "2_2") (pintype "passive"))
      (node (ref "C4") (pin "2") (pinfunction "2_2") (pintype "passive"))
      (node (ref "C42") (pin "2") (pinfunction "2_2") (pintype "passive"))
      (node (ref "C43") (pin "2") (pinfunction "2_2") (pintype "passive"))
      (node (ref "C5") (pin "2") (pinfunction "2_2") (pintype "passive"))
      (node (ref "C6") (pin "2") (pinfunction "2_2") (pintype "passive"))
      (node (ref "C7") (pin "2") (pinfunction "2_2") (pintype "passive"))
      (node (ref "C8") (pin "2") (pinfunction "2_2") (pintype "passive"))
      (node (ref "C9") (pin "2") (pinfunction "2_2") (pintype "passive"))
      (node (ref "D3") (pin "2") (pinfunction "GND_2") (pintype "bidirectional"))
      (node (ref "D4") (pin "1") (pinfunction "K_1") (pintype "bidirectional"))
      (node (ref "EPD_C1") (pin "1") (pinfunction "1_1") (pintype "passive"))
      (node (ref "EPD_C10") (pin "1") (pinfunction "1_1") (pintype "passive"))
      (node (ref "EPD_C11") (pin "1") (pinfunction "1_1") (pintype "passive"))
      (node (ref "EPD_C12") (pin "1") (pinfunction "1_1") (pintype "passive"))
      (node (ref "EPD_C2") (pin "1") (pinfunction "1_1") (pintype "passive"))
      (node (ref "EPD_C5") (pin "1") (pinfunction "1_1") (pintype "passive"))
      (node (ref "EPD_C6") (pin "1") (pinfunction "1_1") (pintype "passive"))
      (node (ref "EPD_C7") (pin "1") (pinfunction "1_1") (pintype "passive"))
      (node (ref "EPD_C8") (pin "1") (pinfunction "1_1") (pintype "passive"))
      (node (ref "EPD_C9") (pin "1") (pinfunction "1_1") (pintype "passive"))
      (node (ref "IC1") (pin "D2") (pinfunction "GND_D2") (pintype "bidirectional"))
      (node (ref "IC2") (pin "B1") (pinfunction "IN/TRIG_B1") (pintype "bidirectional"))
      (node (ref "IC2") (pin "B3") (pinfunction "GND_B3") (pintype "bidirectional"))
      (node (ref "IC3") (pin "8") (pinfunction "GNDIO_8") (pintype "bidirectional"))
      (node (ref "IC3") (pin "9") (pinfunction "GND_9") (pintype "bidirectional"))
      (node (ref "IC9") (pin "B1") (pinfunction "VSEL_B1") (pintype "bidirectional"))
      (node (ref "IC9") (pin "C1") (pinfunction "AGND_C1") (pintype "bidirectional"))
      (node (ref "IC9") (pin "C2") (pinfunction "PGND_1_C2") (pintype "bidirectional"))
      (node (ref "IC9") (pin "C3") (pinfunction "PGND_2_C3") (pintype "bidirectional"))
      (node (ref "J1") (pin "17") (pinfunction "17_17") (pintype "bidirectional"))
      (node (ref "J1") (pin "8") (pinfunction "8_8") (pintype "bidirectional"))
      (node (ref "J1") (pin "MP1") (pinfunction "MP1_MP1") (pintype "bidirectional"))
      (node (ref "J1") (pin "MP2") (pinfunction "MP2_MP2") (pintype "bidirectional"))
      (node (ref "J2") (pin "3") (pinfunction "3_3") (pintype "bidirectional"))
      (node (ref "J2") (pin "5") (pinfunction "5_5") (pintype "bidirectional"))
      (node (ref "J4\\") (pin "A12_B1") (pinfunction "GND_A12_B1") (pintype "power_in"))
      (node (ref "J4\\") (pin "A1_B12") (pinfunction "GND_A1_B12") (pintype "power_in"))
      (node (ref "J4\\") (pin "SH1") (pinfunction "SHIELD_SH1") (pintype "passive"))
      (node (ref "J4\\") (pin "SH2") (pinfunction "SHIELD_SH2") (pintype "passive"))
      (node (ref "J4\\") (pin "SH3") (pinfunction "SHIELD_SH3") (pintype "passive"))
      (node (ref "J4\\") (pin "SH4") (pinfunction "SHIELD_SH4") (pintype "passive"))
      (node (ref "R1_USB") (pin "1") (pinfunction "1_1") (pintype "bidirectional"))
      (node (ref "R2_EP_DR") (pin "1") (pinfunction "1_1") (pintype "bidirectional"))
      (node (ref "R2_USB") (pin "2") (pinfunction "2_2") (pintype "bidirectional"))
      (node (ref "R3") (pin "1") (pinfunction "1_1") (pintype "bidirectional"))
      (node (ref "R9") (pin "1") (pinfunction "1_1") (pintype "bidirectional"))
      (node (ref "R_TYPE_SEL") (pin "1") (pinfunction "1_1") (pintype "bidirectional"))
      (node (ref "SJ1") (pin "1") (pinfunction "1_1") (pintype "passive"))
      (node (ref "SW_DN") (pin "1") (pinfunction "1_1") (pintype "passive"))
      (node (ref "SW_ENT") (pin "1") (pinfunction "1_1") (pintype "passive"))
      (node (ref "SW_UP") (pin "1") (pinfunction "1_1") (pintype "passive"))
      (node (ref "TP_BAT_GND") (pin "TP") (pinfunction "TP_TP") (pintype "input"))
      (node (ref "TP_GND") (pin "TP") (pinfunction "TP_TP") (pintype "input"))
      (node (ref "U1") (pin "P$74") (pinfunction "VSS_PAD_P$74") (pintype "bidirectional"))
      (node (ref "U1") (pin "P$75") (pinfunction "VSS_PAD_P$75") (pintype "bidirectional"))
      (node (ref "U1") (pin "P$76") (pinfunction "VSS_PAD_P$76") (pintype "bidirectional"))
      (node (ref "U1") (pin "P$77") (pinfunction "VSS_PAD_P$77") (pintype "bidirectional"))
      (node (ref "U1") (pin "P$78") (pinfunction "VSS_PAD_P$78") (pintype "bidirectional"))
      (node (ref "U1") (pin "P$79") (pinfunction "VSS_PAD_P$79") (pintype "bidirectional"))
      (node (ref "U1") (pin "P$80") (pinfunction "VSS_PAD_P$80") (pintype "bidirectional"))
      (node (ref "U1") (pin "P$81") (pinfunction "VSS_PAD_P$81") (pintype "bidirectional"))
      (node (ref "U1") (pin "P$82") (pinfunction "VSS_PAD_P$82") (pintype "bidirectional"))
      (node (ref "U1") (pin "P$83") (pinfunction "VSS_PAD_P$83") (pintype "bidirectional"))
      (node (ref "U1") (pin "P$84") (pinfunction "VSS_PAD_P$84") (pintype "bidirectional"))
      (node (ref "U1") (pin "P$85") (pinfunction "VSS_PAD_P$85") (pintype "bidirectional"))
      (node (ref "U1") (pin "P$86") (pinfunction "VSS_PAD_P$86") (pintype "bidirectional"))
      (node (ref "U1") (pin "P$87") (pinfunction "VSS_PAD_P$87") (pintype "bidirectional"))
      (node (ref "U1") (pin "P$88") (pinfunction "VSS_PAD_P$88") (pintype "bidirectional"))
      (node (ref "U1") (pin "P$89") (pinfunction "VSS_PAD_P$89") (pintype "bidirectional"))
      (node (ref "U1") (pin "P$90") (pinfunction "VSS_PAD_P$90") (pintype "bidirectional"))
      (node (ref "U1") (pin "P$B7") (pinfunction "VSS_P$B7") (pintype "power_in"))
      (node (ref "U1") (pin "P$F23") (pinfunction "VSS_PA_P$F23") (pintype "bidirectional"))
      (node (ref "U3") (pin "1") (pinfunction "CTG_1") (pintype "power_in"))
      (node (ref "U3") (pin "4") (pinfunction "GND_4") (pintype "power_in"))
      (node (ref "U3") (pin "6") (pinfunction "QSTRT_6") (pintype "input"))
      (node (ref "U3") (pin "9") (pinfunction "EP_9") (pintype "power_in"))
      (node (ref "X1") (pin "2") (pinfunction "2_2") (pintype "passive"))
      (node (ref "X1") (pin "4") (pinfunction "4_4") (pintype "passive"))
    )
    (net (code "17") (name "HAPTIC_EN") (class "Default")
      (node (ref "IC2") (pin "A1") (pinfunction "EN_A1") (pintype "bidirectional"))
      (node (ref "U1") (pin "P$U1") (pinfunction "P0.12_P$U1") (pintype "bidirectional"))
    )
    (net (code "18") (name "IMU_INT1") (class "Default")
      (node (ref "IC3") (pin "5") (pinfunction "INT1_5") (pintype "bidirectional"))
      (node (ref "U1") (pin "P$N1") (pinfunction "P0.08_P$N1") (pintype "bidirectional"))
    )
    (net (code "19") (name "IMU_INT2") (class "Default")
      (node (ref "IC3") (pin "6") (pinfunction "INT2_6") (pintype "bidirectional"))
      (node (ref "U1") (pin "P$P2") (pinfunction "P1.08_P$P2") (pintype "bidirectional"))
    )
    (net (code "20") (name "LX1") (class "Default")
      (node (ref "IC9") (pin "B2") (pinfunction "SW1_1_B2") (pintype "bidirectional"))
      (node (ref "IC9") (pin "B3") (pinfunction "SW1_2_B3") (pintype "bidirectional"))
      (node (ref "L7") (pin "1") (pinfunction "1_1") (pintype "bidirectional"))
    )
    (net (code "21") (name "LX2") (class "Default")
      (node (ref "IC9") (pin "D2") (pinfunction "SW2_1_D2") (pintype "bidirectional"))
      (node (ref "IC9") (pin "D3") (pinfunction "SW2_2_D3") (pintype "bidirectional"))
      (node (ref "L7") (pin "2") (pinfunction "2_2") (pintype "bidirectional"))
    )
    (net (code "22") (name "MOSI") (class "Default")
      (node (ref "J1") (pin "14") (pinfunction "14_14") (pintype "bidirectional"))
      (node (ref "U1") (pin "P$B13") (pinfunction "P0.03/AIN1_P$B13") (pintype "bidirectional"))
    )
    (net (code "23") (name "Net-(C30-Pad2)") (class "Default")
      (node (ref "C30") (pin "2") (pinfunction "2_2") (pintype "passive"))
      (node (ref "R5") (pin "1") (pinfunction "1_1") (pintype "bidirectional"))
    )
    (net (code "24") (name "Net-(C31-Pad2)") (class "Default")
      (node (ref "C31") (pin "2") (pinfunction "2_2") (pintype "passive"))
      (node (ref "R8") (pin "1") (pinfunction "1_1") (pintype "bidirectional"))
    )
    (net (code "25") (name "Net-(D2-K)") (class "Default")
      (node (ref "C2-EP-DR") (pin "1") (pinfunction "1_1") (pintype "passive"))
      (node (ref "D2") (pin "1") (pinfunction "K_1") (pintype "bidirectional"))
      (node (ref "D4") (pin "2") (pinfunction "A_2") (pintype "bidirectional"))
    )
    (net (code "26") (name "Net-(D5-A)") (class "Default")
      (node (ref "C2-EP-DR") (pin "2") (pinfunction "2_2") (pintype "passive"))
      (node (ref "D5") (pin "2") (pinfunction "A_2") (pintype "bidirectional"))
      (node (ref "L5") (pin "1") (pinfunction "1_1") (pintype "passive"))
      (node (ref "Q3") (pin "3") (pinfunction "D_3") (pintype "bidirectional"))
    )
    (net (code "27") (name "Net-(EPD_C1-Pad2)") (class "Default")
      (node (ref "EPD_C1") (pin "2") (pinfunction "2_2") (pintype "passive"))
      (node (ref "J1") (pin "5") (pinfunction "5_5") (pintype "bidirectional"))
    )
    (net (code "28") (name "Net-(EPD_C2-Pad2)") (class "Default")
      (node (ref "EPD_C2") (pin "2") (pinfunction "2_2") (pintype "passive"))
      (node (ref "J1") (pin "4") (pinfunction "4_4") (pintype "bidirectional"))
    )
    (net (code "29") (name "Net-(EPD_C6-Pad2)") (class "Default")
      (node (ref "EPD_C6") (pin "2") (pinfunction "2_2") (pintype "passive"))
      (node (ref "J1") (pin "18") (pinfunction "18_18") (pintype "bidirectional"))
    )
    (net (code "30") (name "Net-(EPD_C7-Pad2)") (class "Default")
      (node (ref "EPD_C7") (pin "2") (pinfunction "2_2") (pintype "passive"))
      (node (ref "J1") (pin "19") (pinfunction "19_19") (pintype "bidirectional"))
    )
    (net (code "31") (name "Net-(EPD_C8-Pad2)") (class "Default")
      (node (ref "EPD_C8") (pin "2") (pinfunction "2_2") (pintype "passive"))
      (node (ref "J1") (pin "20") (pinfunction "20_20") (pintype "bidirectional"))
    )
    (net (code "32") (name "Net-(EPD_C10-Pad2)") (class "Default")
      (node (ref "EPD_C10") (pin "2") (pinfunction "2_2") (pintype "passive"))
      (node (ref "J1") (pin "22") (pinfunction "22_22") (pintype "bidirectional"))
    )
    (net (code "33") (name "Net-(EPD_C12-Pad2)") (class "Default")
      (node (ref "EPD_C12") (pin "2") (pinfunction "2_2") (pintype "passive"))
      (node (ref "J1") (pin "24") (pinfunction "24_24") (pintype "bidirectional"))
    )
    (net (code "34") (name "Net-(IC1-TS{slash}MR)") (class "Default")
      (node (ref "IC1") (pin "D1") (pinfunction "TS/MR_D1") (pintype "bidirectional"))
      (node (ref "R9") (pin "2") (pinfunction "2_2") (pintype "bidirectional"))
    )
    (net (code "35") (name "Net-(IC2-REG)") (class "Default")
      (node (ref "C32") (pin "2") (pinfunction "2_2") (pintype "passive"))
      (node (ref "IC2") (pin "A2") (pinfunction "REG_A2") (pintype "bidirectional"))
    )
    (net (code "36") (name "Net-(IC3-SDO)") (class "Default")
      (node (ref "IC3") (pin "1") (pinfunction "SDO_1") (pintype "bidirectional"))
      (node (ref "R3") (pin "2") (pinfunction "2_2") (pintype "bidirectional"))
    )
    (net (code "37") (name "Net-(IC9-SCL)") (class "Default")
      (node (ref "IC9") (pin "D1") (pinfunction "SCL_D1") (pintype "bidirectional"))
      (node (ref "R4") (pin "2") (pinfunction "2_2") (pintype "bidirectional"))
    )
    (net (code "38") (name "Net-(IC9-SDA)") (class "Default")
      (node (ref "IC9") (pin "E1") (pinfunction "SDA_E1") (pintype "bidirectional"))
      (node (ref "R2") (pin "2") (pinfunction "2_2") (pintype "bidirectional"))
    )
    (net (code "39") (name "Net-(J4\\-CC1)") (class "Default")
      (node (ref "J4\\") (pin "A5") (pinfunction "CC1_A5") (pintype "bidirectional"))
      (node (ref "R1_USB") (pin "2") (pinfunction "2_2") (pintype "bidirectional"))
    )
    (net (code "40") (name "Net-(J4\\-CC2)") (class "Default")
      (node (ref "J4\\") (pin "B5") (pinfunction "CC2_B5") (pintype "bidirectional"))
      (node (ref "R2_USB") (pin "1") (pinfunction "1_1") (pintype "bidirectional"))
    )
    (net (code "41") (name "Net-(L2-Pad2)") (class "Default")
      (node (ref "L2") (pin "2") (pinfunction "2_2") (pintype "passive"))
      (node (ref "L3") (pin "1") (pinfunction "1_1") (pintype "passive"))
    )
    (net (code "42") (name "Net-(R1_EP_DR-Pad1)") (class "Default")
      (node (ref "R1_EP_DR") (pin "1") (pinfunction "1_1") (pintype "bidirectional"))
      (node (ref "R_TYPE_SEL") (pin "2") (pinfunction "2_2") (pintype "bidirectional"))
      (node (ref "SJ1") (pin "2") (pinfunction "2_2") (pintype "passive"))
    )
    (net (code "43") (name "Net-(U1-ANT)") (class "Default")
      (node (ref "C3") (pin "1") (pinfunction "1_1") (pintype "passive"))
      (node (ref "L1") (pin "1") (pinfunction "1_1") (pintype "passive"))
      (node (ref "U1") (pin "P$H23") (pinfunction "ANT_P$H23") (pintype "bidirectional"))
    )
    (net (code "44") (name "Net-(U1-DCC)") (class "Default")
      (node (ref "L2") (pin "1") (pinfunction "1_1") (pintype "passive"))
      (node (ref "U1") (pin "P$B3") (pinfunction "DCC_P$B3") (pintype "output"))
    )
    (net (code "45") (name "Net-(U1-DEC2)") (class "Default")
      (node (ref "C13") (pin "1") (pinfunction "1_1") (pintype "passive"))
      (node (ref "U1") (pin "P$A18") (pinfunction "DEC2_P$A18") (pintype "bidirectional"))
    )
    (net (code "46") (name "Net-(U1-DEC3V3)") (class "Default")
      (node (ref "C20") (pin "1") (pinfunction "1_1") (pintype "passive"))
      (node (ref "U1") (pin "P$AC5") (pinfunction "DEC3V3_P$AC5") (pintype "bidirectional"))
    )
    (net (code "47") (name "Net-(U1-DEC5)") (class "Default")
      (node (ref "C9") (pin "1") (pinfunction "1_1") (pintype "passive"))
      (node (ref "U1") (pin "P$N24") (pinfunction "DEC5_P$N24") (pintype "bidirectional"))
    )
    (net (code "48") (name "Net-(U1-XC1)") (class "Default")
      (node (ref "C1") (pin "1") (pinfunction "1_1") (pintype "passive"))
      (node (ref "U1") (pin "P$B24") (pinfunction "XC1_P$B24") (pintype "input"))
      (node (ref "X1") (pin "1") (pinfunction "1_1") (pintype "passive"))
    )
    (net (code "49") (name "Net-(U1-XC2)") (class "Default")
      (node (ref "C2") (pin "1") (pinfunction "1_1") (pintype "passive"))
      (node (ref "U1") (pin "P$A23") (pinfunction "XC2_P$A23") (pintype "output"))
      (node (ref "X1") (pin "3") (pinfunction "3_3") (pintype "passive"))
    )
    (net (code "50") (name "OUT+") (class "Default")
      (node (ref "IC2") (pin "A3") (pinfunction "OUT+_A3") (pintype "bidirectional"))
      (node (ref "TP_OP") (pin "TP") (pinfunction "TP_TP") (pintype "input"))
    )
    (net (code "51") (name "OUT-") (class "Default")
      (node (ref "IC2") (pin "C3") (pinfunction "OUT-_C3") (pintype "bidirectional"))
      (node (ref "TP_ON") (pin "TP") (pinfunction "TP_TP") (pintype "input"))
    )
    (net (code "52") (name "P0.00{slash}XL1") (class "Default")
      (node (ref "C17") (pin "2") (pinfunction "2_2") (pintype "passive"))
      (node (ref "U1") (pin "P$D2") (pinfunction "P0.00/XL1_P$D2") (pintype "bidirectional"))
      (node (ref "X2") (pin "1") (pinfunction "1_1") (pintype "passive"))
    )
    (net (code "53") (name "P0.01{slash}XL2") (class "Default")
      (node (ref "C18") (pin "2") (pinfunction "2_2") (pintype "passive"))
      (node (ref "U1") (pin "P$F2") (pinfunction "P0.01/XL2_P$F2") (pintype "bidirectional"))
      (node (ref "X2") (pin "2") (pinfunction "2_2") (pintype "passive"))
    )
    (net (code "54") (name "P0.04") (class "Default")
      (node (ref "U1") (pin "P$J1") (pinfunction "P0.04/AIN2_P$J1") (pintype "bidirectional"))
    )
    (net (code "55") (name "P0.09") (class "Default")
      (node (ref "U1") (pin "P$L24") (pinfunction "P0.09/NFC1_P$L24") (pintype "bidirectional"))
    )
    (net (code "56") (name "P0.13") (class "Default")
      (node (ref "SW_UP") (pin "2") (pinfunction "2_2") (pintype "passive"))
      (node (ref "U1") (pin "P$AD8") (pinfunction "P0.13_P$AD8") (pintype "bidirectional"))
    )
    (net (code "57") (name "P0.14") (class "Default")
      (node (ref "SW_ENT") (pin "2") (pinfunction "2_2") (pintype "passive"))
      (node (ref "U1") (pin "P$AC9") (pinfunction "P0.14_P$AC9") (pintype "bidirectional"))
    )
    (net (code "58") (name "P0.19") (class "Default")
      (node (ref "U1") (pin "P$AC15") (pinfunction "P0.19_P$AC15") (pintype "bidirectional"))
    )
    (net (code "59") (name "P0.20") (class "Default")
      (node (ref "U1") (pin "P$AD16") (pinfunction "P0.20_P$AD16") (pintype "bidirectional"))
    )
    (net (code "60") (name "P0.21") (class "Default")
      (node (ref "U1") (pin "P$AC17") (pinfunction "P0.21_P$AC17") (pintype "bidirectional"))
    )
    (net (code "61") (name "P0.22") (class "Default")
      (node (ref "U1") (pin "P$AD18") (pinfunction "P0.22_P$AD18") (pintype "bidirectional"))
    )
    (net (code "62") (name "P0.23") (class "Default")
      (node (ref "U1") (pin "P$AC19") (pinfunction "P0.23_P$AC19") (pintype "bidirectional"))
    )
    (net (code "63") (name "P0.24") (class "Default")
      (node (ref "U1") (pin "P$AD20") (pinfunction "P0.24_P$AD20") (pintype "bidirectional"))
    )
    (net (code "64") (name "P0.25") (class "Default")
      (node (ref "U1") (pin "P$AC21") (pinfunction "P0.25_P$AC21") (pintype "bidirectional"))
    )
    (net (code "65") (name "P0.28") (class "Default")
      (node (ref "U1") (pin "P$B11") (pinfunction "P0.28/AIN4_P$B11") (pintype "bidirectional"))
    )
    (net (code "66") (name "P0.29") (class "Default")
      (node (ref "U1") (pin "P$A10") (pinfunction "P0.29/AIN5_P$A10") (pintype "bidirectional"))
    )
    (net (code "67") (name "P0.30") (class "Default")
      (node (ref "U1") (pin "P$B9") (pinfunction "P0.30/AIN6_P$B9") (pintype "bidirectional"))
    )
    (net (code "68") (name "P0.31") (class "Default")
      (node (ref "U1") (pin "P$A8") (pinfunction "P0.31/AIN7_P$A8") (pintype "bidirectional"))
    )
    (net (code "69") (name "P1.01") (class "Default")
      (node (ref "Q1") (pin "1") (pinfunction "G_1") (pintype "bidirectional"))
      (node (ref "R_PWR_EPD") (pin "1") (pinfunction "1_1") (pintype "bidirectional"))
      (node (ref "U1") (pin "P$Y23") (pinfunction "P1.01_P$Y23") (pintype "bidirectional"))
    )
    (net (code "70") (name "P1.02") (class "Default")
      (node (ref "C29") (pin "2") (pinfunction "2_2") (pintype "passive"))
      (node (ref "R7") (pin "1") (pinfunction "1_1") (pintype "bidirectional"))
      (node (ref "SW_DN") (pin "2") (pinfunction "2_2") (pintype "passive"))
      (node (ref "U1") (pin "P$W24") (pinfunction "P1.02_P$W24") (pintype "bidirectional"))
    )
    (net (code "71") (name "P1.03") (class "Default")
      (node (ref "U1") (pin "P$V23") (pinfunction "P1.03_P$V23") (pintype "bidirectional"))
    )
    (net (code "72") (name "P1.04") (class "Default")
      (node (ref "U1") (pin "P$U24") (pinfunction "P1.04_P$U24") (pintype "bidirectional"))
    )
    (net (code "73") (name "P1.05") (class "Default")
      (node (ref "U1") (pin "P$T23") (pinfunction "P1.05_P$T23") (pintype "bidirectional"))
    )
    (net (code "74") (name "P1.06") (class "Default")
      (node (ref "U1") (pin "P$R24") (pinfunction "P1.06_P$R24") (pintype "bidirectional"))
    )
    (net (code "75") (name "P1.07") (class "Default")
      (node (ref "U1") (pin "P$P23") (pinfunction "P1.07_P$P23") (pintype "bidirectional"))
    )
    (net (code "76") (name "P1.09") (class "Default")
      (node (ref "U1") (pin "P$R1") (pinfunction "P1.09_P$R1") (pintype "bidirectional"))
    )
    (net (code "77") (name "P1.10") (class "Default")
      (node (ref "U1") (pin "P$A20") (pinfunction "P1.10_P$A20") (pintype "bidirectional"))
    )
    (net (code "78") (name "P1.11") (class "Default")
      (node (ref "U1") (pin "P$B19") (pinfunction "P1.11_P$B19") (pintype "bidirectional"))
    )
    (net (code "79") (name "P1.12") (class "Default")
      (node (ref "U1") (pin "P$B17") (pinfunction "P1.12_P$B17") (pintype "bidirectional"))
    )
    (net (code "80") (name "P1.13") (class "Default")
      (node (ref "U1") (pin "P$A16") (pinfunction "P1.13_P$A16") (pintype "bidirectional"))
    )
    (net (code "81") (name "P1.14") (class "Default")
      (node (ref "U1") (pin "P$B15") (pinfunction "P1.14_P$B15") (pintype "bidirectional"))
    )
    (net (code "82") (name "P1.15") (class "Default")
      (node (ref "U1") (pin "P$A14") (pinfunction "P1.15_P$A14") (pintype "bidirectional"))
    )
    (net (code "83") (name "PMIC_INT") (class "Default")
      (node (ref "IC1") (pin "A1") (pinfunction "~{INT}_A1") (pintype "bidirectional"))
      (node (ref "U1") (pin "P$T2") (pinfunction "P0.11_P$T2") (pintype "bidirectional"))
    )
    (net (code "84") (name "PO.26") (class "Default")
      (node (ref "U1") (pin "P$G1") (pinfunction "P0.26_P$G1") (pintype "bidirectional"))
    )
    (net (code "85") (name "PO.27") (class "Default")
      (node (ref "U1") (pin "P$H2") (pinfunction "P0.27_P$H2") (pintype "bidirectional"))
    )
    (net (code "86") (name "PREVGH") (class "Default")
      (node (ref "D5") (pin "1") (pinfunction "K_1") (pintype "bidirectional"))
      (node (ref "EPD_C9") (pin "2") (pinfunction "2_2") (pintype "passive"))
      (node (ref "J1") (pin "21") (pinfunction "21_21") (pintype "bidirectional"))
    )
    (net (code "87") (name "PREVGL") (class "Default")
      (node (ref "D2") (pin "2") (pinfunction "A_2") (pintype "bidirectional"))
      (node (ref "EPD_C11") (pin "2") (pinfunction "2_2") (pintype "passive"))
      (node (ref "J1") (pin "23") (pinfunction "23_23") (pintype "bidirectional"))
    )
    (net (code "88") (name "RESE") (class "Default")
      (node (ref "J1") (pin "3") (pinfunction "3_3") (pintype "bidirectional"))
      (node (ref "Q3") (pin "2") (pinfunction "S_2") (pintype "bidirectional"))
      (node (ref "R1_EP_DR") (pin "2") (pinfunction "2_2") (pintype "bidirectional"))
    )
    (net (code "89") (name "RESET") (class "Default")
      (node (ref "J2") (pin "6") (pinfunction "6_6") (pintype "bidirectional"))
      (node (ref "TP_RESET") (pin "TP") (pinfunction "TP_TP") (pintype "input"))
      (node (ref "U1") (pin "P$AC13") (pinfunction "P0.18/RESET_P$AC13") (pintype "bidirectional"))
    )
    (net (code "90") (name "RF") (class "Default")
      (node (ref "ANT1") (pin "1") (pinfunction "FEED_1") (pintype "input"))
      (node (ref "C22") (pin "1") (pinfunction "1_1") (pintype "passive"))
      (node (ref "C4") (pin "1") (pinfunction "1_1") (pintype "passive"))
      (node (ref "L1") (pin "2") (pinfunction "2_2") (pintype "passive"))
    )
    (net (code "91") (name "SCK") (class "Default")
      (node (ref "J1") (pin "13") (pinfunction "13_13") (pintype "bidirectional"))
      (node (ref "U1") (pin "P$A12") (pinfunction "P0.02/AIN0_P$A12") (pintype "bidirectional"))
    )
    (net (code "92") (name "SCL") (class "Default")
      (node (ref "IC1") (pin "B1") (pinfunction "SCL_B1") (pintype "bidirectional"))
      (node (ref "IC2") (pin "C1") (pinfunction "SCL_C1") (pintype "bidirectional"))
      (node (ref "IC3") (pin "12") (pinfunction "SCX_12") (pintype "bidirectional"))
      (node (ref "R17") (pin "2") (pinfunction "2_2") (pintype "bidirectional"))
      (node (ref "R4") (pin "1") (pinfunction "1_1") (pintype "bidirectional"))
      (node (ref "TP_SCL") (pin "TP") (pinfunction "TP_TP") (pintype "input"))
      (node (ref "U1") (pin "P$M2") (pinfunction "P0.07_P$M2") (pintype "bidirectional"))
      (node (ref "U3") (pin "7") (pinfunction "SCL_7") (pintype "input"))
    )
    (net (code "93") (name "SDA") (class "Default")
      (node (ref "IC1") (pin "C1") (pinfunction "SDA_C1") (pintype "bidirectional"))
      (node (ref "IC2") (pin "B2") (pinfunction "SDA_B2") (pintype "bidirectional"))
      (node (ref "IC3") (pin "2") (pinfunction "SDX_2") (pintype "bidirectional"))
      (node (ref "R18") (pin "2") (pinfunction "2_2") (pintype "bidirectional"))
      (node (ref "R2") (pin "1") (pinfunction "1_1") (pintype "bidirectional"))
      (node (ref "TP_SDA") (pin "TP") (pinfunction "TP_TP") (pintype "input"))
      (node (ref "U1") (pin "P$L1") (pinfunction "P0.06_P$L1") (pintype "bidirectional"))
      (node (ref "U3") (pin "8") (pinfunction "SDA_8") (pintype "bidirectional"))
    )
    (net (code "94") (name "SWDCLK") (class "Default")
      (node (ref "J2") (pin "4") (pinfunction "4_4") (pintype "bidirectional"))
      (node (ref "TP_SWDCLK") (pin "TP") (pinfunction "TP_TP") (pintype "input"))
      (node (ref "U1") (pin "P$AA24") (pinfunction "SWDCLK_P$AA24") (pintype "input"))
    )
    (net (code "95") (name "SWDIO") (class "Default")
      (node (ref "J2") (pin "2") (pinfunction "2_2") (pintype "bidirectional"))
      (node (ref "TP_SWDIO") (pin "TP") (pinfunction "TP_TP") (pintype "input"))
      (node (ref "U1") (pin "P$AC24") (pinfunction "SWDIO_P$AC24") (pintype "bidirectional"))
    )
    (net (code "96") (name "SWO") (class "Default")
      (node (ref "TP_SWO") (pin "TP") (pinfunction "TP_TP") (pintype "input"))
      (node (ref "U1") (pin "P$AD22") (pinfunction "P1.00_P$AD22") (pintype "bidirectional"))
    )
    (net (code "97") (name "VBAT") (class "Default")
      (node (ref "C27") (pin "2") (pinfunction "2_2") (pintype "passive"))
      (node (ref "C37") (pin "2") (pinfunction "2_2") (pintype "passive"))
      (node (ref "IC1") (pin "C2") (pinfunction "BAT_C2") (pintype "bidirectional"))
      (node (ref "TP_VBAT") (pin "TP") (pinfunction "TP_TP") (pintype "input"))
      (node (ref "U3") (pin "2") (pinfunction "CELL_2") (pintype "power_in"))
      (node (ref "U3") (pin "3") (pinfunction "VDD_3") (pintype "power_in"))
    )
    (net (code "98") (name "VBUS") (class "Default")
      (node (ref "C21") (pin "1") (pinfunction "1_1") (pintype "passive"))
      (node (ref "C38") (pin "2") (pinfunction "2_2") (pintype "passive"))
      (node (ref "C42") (pin "1") (pinfunction "1_1") (pintype "passive"))
      (node (ref "C43") (pin "1") (pinfunction "1_1") (pintype "passive"))
      (node (ref "D3") (pin "5") (pinfunction "VBUS_5") (pintype "bidirectional"))
      (node (ref "IC1") (pin "A2") (pinfunction "IN_A2") (pintype "bidirectional"))
      (node (ref "J4\\") (pin "A4_B9") (pinfunction "VBUS_A4_B9") (pintype "power_in"))
      (node (ref "J4\\") (pin "A9_B4") (pinfunction "VBUS_A9_B4") (pintype "power_in"))
      (node (ref "U1") (pin "P$AD2") (pinfunction "VBUS_P$AD2") (pintype "power_in"))
    )
    (net (code "99") (name "VREG") (class "Default")
      (node (ref "C23") (pin "1") (pinfunction "1_1") (pintype "passive"))
      (node (ref "C24") (pin "2") (pinfunction "2_2") (pintype "passive"))
      (node (ref "C39") (pin "1") (pinfunction "1_1") (pintype "passive"))
      (node (ref "IC1") (pin "B2") (pinfunction "SYS_B2") (pintype "bidirectional"))
      (node (ref "IC9") (pin "A1") (pinfunction "EN_A1") (pintype "bidirectional"))
      (node (ref "IC9") (pin "A2") (pinfunction "VIN_1_A2") (pintype "bidirectional"))
      (node (ref "IC9") (pin "A3") (pinfunction "VIN_2_A3") (pintype "bidirectional"))
      (node (ref "TP_VREG") (pin "TP") (pinfunction "TP_TP") (pintype "input"))
    )
    (net (code "100") (name "unconnected-(ANT1-NC-Pad2)") (class "Default")
      (node (ref "ANT1") (pin "2") (pinfunction "NC_2") (pintype "no_connect"))
    )
    (net (code "101") (name "unconnected-(IC3-ASCL-Pad11)") (class "Default")
      (node (ref "IC3") (pin "11") (pinfunction "ASCL_11") (pintype "bidirectional"))
    )
    (net (code "102") (name "unconnected-(IC3-ASDA-Pad4)") (class "Default")
      (node (ref "IC3") (pin "4") (pinfunction "ASDA_4") (pintype "bidirectional"))
    )
    (net (code "103") (name "unconnected-(J1-Pad1)") (class "Default")
      (node (ref "J1") (pin "1") (pinfunction "1_1") (pintype "bidirectional"))
    )
    (net (code "104") (name "unconnected-(J1-Pad6)") (class "Default")
      (node (ref "J1") (pin "6") (pinfunction "6_6") (pintype "bidirectional"))
    )
    (net (code "105") (name "unconnected-(J1-Pad7)") (class "Default")
      (node (ref "J1") (pin "7") (pinfunction "7_7") (pintype "bidirectional"))
    )
    (net (code "106") (name "unconnected-(J4\\-SBU1-PadA8)") (class "Default")
      (node (ref "J4\\") (pin "A8") (pinfunction "SBU1_A8") (pintype "bidirectional"))
    )
    (net (code "107") (name "unconnected-(J4\\-SBU2-PadB8)") (class "Default")
      (node (ref "J4\\") (pin "B8") (pinfunction "SBU2_B8") (pintype "bidirectional"))
    )
    (net (code "108") (name "unconnected-(U1-DCCH-PadP$AB2)") (class "Default")
      (node (ref "U1") (pin "P$AB2") (pinfunction "DCCH_P$AB2") (pintype "bidirectional"))
    )
  )
)
